# Drivers.net
KiCad netlist of a schematic drawn in EAGLE
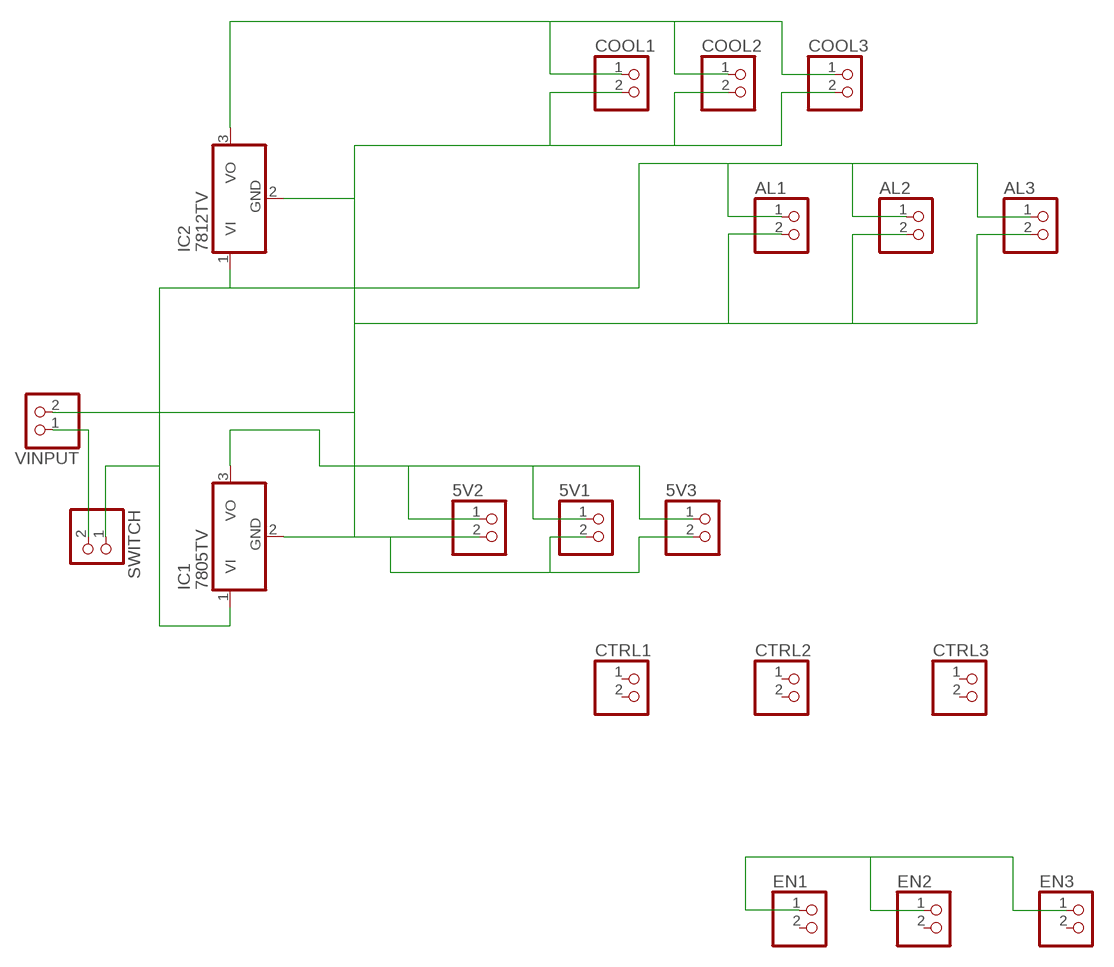
[diagram p0: schematic, sheet 1]

(export (version "E")
  (design (tool "Eeschema 10.0.6"))
  (components
    (comp (ref "5V1")
      (value "PINHD-1X2")
      (footprint "eagle-import:1X02")
      (libsource (lib "eagle-import") (part "PINHD-1X2"))
    )
    (comp (ref "5V2")
      (value "PINHD-1X2")
      (footprint "eagle-import:1X02")
      (libsource (lib "eagle-import") (part "PINHD-1X2"))
    )
    (comp (ref "5V3")
      (value "PINHD-1X2")
      (footprint "eagle-import:1X02")
      (libsource (lib "eagle-import") (part "PINHD-1X2"))
    )
    (comp (ref "AL1")
      (value "PINHD-1X2")
      (footprint "eagle-import:1X02")
      (libsource (lib "eagle-import") (part "PINHD-1X2"))
    )
    (comp (ref "AL2")
      (value "PINHD-1X2")
      (footprint "eagle-import:1X02")
      (libsource (lib "eagle-import") (part "PINHD-1X2"))
    )
    (comp (ref "AL3")
      (value "PINHD-1X2")
      (footprint "eagle-import:1X02")
      (libsource (lib "eagle-import") (part "PINHD-1X2"))
    )
    (comp (ref "COOL1")
      (value "PINHD-1X2")
      (footprint "eagle-import:1X02")
      (libsource (lib "eagle-import") (part "PINHD-1X2"))
    )
    (comp (ref "COOL2")
      (value "PINHD-1X2")
      (footprint "eagle-import:1X02")
      (libsource (lib "eagle-import") (part "PINHD-1X2"))
    )
    (comp (ref "COOL3")
      (value "PINHD-1X2")
      (footprint "eagle-import:1X02")
      (libsource (lib "eagle-import") (part "PINHD-1X2"))
    )
    (comp (ref "CTRL1")
      (value "PINHD-1X2")
      (footprint "eagle-import:1X02")
      (libsource (lib "eagle-import") (part "PINHD-1X2"))
    )
    (comp (ref "CTRL2")
      (value "PINHD-1X2")
      (footprint "eagle-import:1X02")
      (libsource (lib "eagle-import") (part "PINHD-1X2"))
    )
    (comp (ref "CTRL3")
      (value "PINHD-1X2")
      (footprint "eagle-import:1X02")
      (libsource (lib "eagle-import") (part "PINHD-1X2"))
    )
    (comp (ref "EN1")
      (value "PINHD-1X2")
      (footprint "eagle-import:1X02")
      (libsource (lib "eagle-import") (part "PINHD-1X2"))
    )
    (comp (ref "EN2")
      (value "PINHD-1X2")
      (footprint "eagle-import:1X02")
      (libsource (lib "eagle-import") (part "PINHD-1X2"))
    )
    (comp (ref "EN3")
      (value "PINHD-1X2")
      (footprint "eagle-import:1X02")
      (libsource (lib "eagle-import") (part "PINHD-1X2"))
    )
    (comp (ref "IC1")
      (value "7805TV")
      (footprint "eagle-import:TO220V")
      (libsource (lib "eagle-import") (part "78TV05"))
    )
    (comp (ref "IC2")
      (value "7812TV")
      (footprint "eagle-import:TO220V")
      (libsource (lib "eagle-import") (part "78TV12"))
    )
    (comp (ref "SWITCH")
      (value "PINHD-1X2")
      (footprint "eagle-import:1X02")
      (libsource (lib "eagle-import") (part "PINHD-1X2"))
    )
    (comp (ref "VINPUT")
      (value "PINHD-1X2")
      (footprint "eagle-import:1X02")
      (libsource (lib "eagle-import") (part "PINHD-1X2"))
    )
  )
  (nets
    (net (code "1") (name "Net-(EN1-Pad1)") (class "Default")
      (node (ref "EN1") (pin "1") (pinfunction "1_1") (pintype "passive"))
      (node (ref "EN2") (pin "1") (pinfunction "1_1") (pintype "passive"))
      (node (ref "EN3") (pin "1") (pinfunction "1_1") (pintype "passive"))
    )
    (net (code "2") (name "Net-(IC1-GND)") (class "Default")
      (node (ref "5V1") (pin "2") (pinfunction "2_2") (pintype "passive"))
      (node (ref "5V2") (pin "2") (pinfunction "2_2") (pintype "passive"))
      (node (ref "5V3") (pin "2") (pinfunction "2_2") (pintype "passive"))
      (node (ref "AL1") (pin "2") (pinfunction "2_2") (pintype "passive"))
      (node (ref "AL2") (pin "2") (pinfunction "2_2") (pintype "passive"))
      (node (ref "AL3") (pin "2") (pinfunction "2_2") (pintype "passive"))
      (node (ref "COOL1") (pin "2") (pinfunction "2_2") (pintype "passive"))
      (node (ref "COOL2") (pin "2") (pinfunction "2_2") (pintype "passive"))
      (node (ref "COOL3") (pin "2") (pinfunction "2_2") (pintype "passive"))
      (node (ref "IC1") (pin "2") (pinfunction "GND_2") (pintype "passive"))
      (node (ref "IC2") (pin "2") (pinfunction "GND_2") (pintype "passive"))
      (node (ref "VINPUT") (pin "2") (pinfunction "2_2") (pintype "passive"))
    )
    (net (code "3") (name "Net-(IC1-VI)") (class "Default")
      (node (ref "AL1") (pin "1") (pinfunction "1_1") (pintype "passive"))
      (node (ref "AL2") (pin "1") (pinfunction "1_1") (pintype "passive"))
      (node (ref "AL3") (pin "1") (pinfunction "1_1") (pintype "passive"))
      (node (ref "IC1") (pin "1") (pinfunction "VI_1") (pintype "input"))
      (node (ref "IC2") (pin "1") (pinfunction "VI_1") (pintype "input"))
      (node (ref "SWITCH") (pin "1") (pinfunction "1_1") (pintype "passive"))
    )
    (net (code "4") (name "Net-(IC1-VO)") (class "Default")
      (node (ref "5V1") (pin "1") (pinfunction "1_1") (pintype "passive"))
      (node (ref "5V2") (pin "1") (pinfunction "1_1") (pintype "passive"))
      (node (ref "5V3") (pin "1") (pinfunction "1_1") (pintype "passive"))
      (node (ref "IC1") (pin "3") (pinfunction "VO_3") (pintype "passive"))
    )
    (net (code "5") (name "Net-(IC2-VO)") (class "Default")
      (node (ref "COOL1") (pin "1") (pinfunction "1_1") (pintype "passive"))
      (node (ref "COOL2") (pin "1") (pinfunction "1_1") (pintype "passive"))
      (node (ref "COOL3") (pin "1") (pinfunction "1_1") (pintype "passive"))
      (node (ref "IC2") (pin "3") (pinfunction "VO_3") (pintype "passive"))
    )
    (net (code "6") (name "Net-(SWITCH-Pad2)") (class "Default")
      (node (ref "SWITCH") (pin "2") (pinfunction "2_2") (pintype "passive"))
      (node (ref "VINPUT") (pin "1") (pinfunction "1_1") (pintype "passive"))
    )
    (net (code "7") (name "unconnected-(CTRL1-Pad1)") (class "Default")
      (node (ref "CTRL1") (pin "1") (pinfunction "1_1") (pintype "passive"))
    )
    (net (code "8") (name "unconnected-(CTRL1-Pad2)") (class "Default")
      (node (ref "CTRL1") (pin "2") (pinfunction "2_2") (pintype "passive"))
    )
    (net (code "9") (name "unconnected-(CTRL2-Pad1)") (class "Default")
      (node (ref "CTRL2") (pin "1") (pinfunction "1_1") (pintype "passive"))
    )
    (net (code "10") (name "unconnected-(CTRL2-Pad2)") (class "Default")
      (node (ref "CTRL2") (pin "2") (pinfunction "2_2") (pintype "passive"))
    )
    (net (code "11") (name "unconnected-(CTRL3-Pad1)") (class "Default")
      (node (ref "CTRL3") (pin "1") (pinfunction "1_1") (pintype "passive"))
    )
    (net (code "12") (name "unconnected-(CTRL3-Pad2)") (class "Default")
      (node (ref "CTRL3") (pin "2") (pinfunction "2_2") (pintype "passive"))
    )
    (net (code "13") (name "unconnected-(EN1-Pad2)") (class "Default")
      (node (ref "EN1") (pin "2") (pinfunction "2_2") (pintype "passive"))
    )
    (net (code "14") (name "unconnected-(EN2-Pad2)") (class "Default")
      (node (ref "EN2") (pin "2") (pinfunction "2_2") (pintype "passive"))
    )
    (net (code "15") (name "unconnected-(EN3-Pad2)") (class "Default")
      (node (ref "EN3") (pin "2") (pinfunction "2_2") (pintype "passive"))
    )
  )
)
